# TranslationDir8Chan.net
KiCad netlist of a schematic drawn in Altium Designer
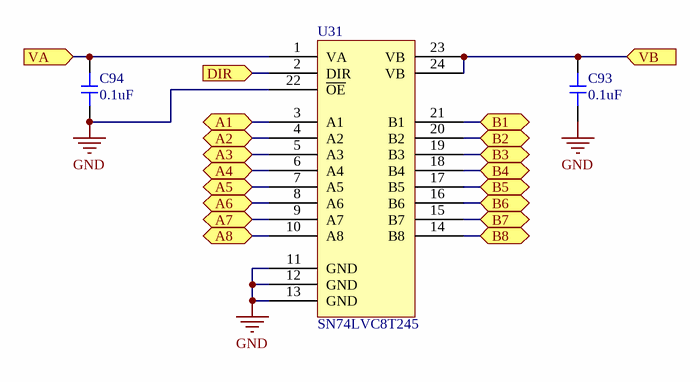
[diagram p0: TranslationDir8Chan.SchDoc]

(export (version "E")
  (design (tool "Eeschema 10.0.6"))
  (components
    (comp (ref "C93")
      (value "0.1uF")
      (footprint "0603-CAP")
      (description "Capacitor")
      (libsource (lib "AMDC") (part "Capacitor"))
    )
    (comp (ref "C94")
      (value "0.1uF")
      (footprint "0603-CAP")
      (description "Capacitor")
      (libsource (lib "AMDC") (part "Capacitor"))
    )
    (comp (ref "U31")
      (value "SN74LVC8T245")
      (footprint "TSOP65P640X120-24N")
      (description "IC BUS TRANSCVR 8BIT 24TSSOP")
      (libsource (lib "AMDC") (part "SN74LVC8T245PWR"))
    )
  )
  (nets
    (net (code "1") (name "/A1") (class "Default")
      (node (ref "U31") (pin "3") (pinfunction "A1_3") (pintype "passive"))
    )
    (net (code "2") (name "/A2") (class "Default")
      (node (ref "U31") (pin "4") (pinfunction "A2_4") (pintype "passive"))
    )
    (net (code "3") (name "/A3") (class "Default")
      (node (ref "U31") (pin "5") (pinfunction "A3_5") (pintype "passive"))
    )
    (net (code "4") (name "/A4") (class "Default")
      (node (ref "U31") (pin "6") (pinfunction "A4_6") (pintype "passive"))
    )
    (net (code "5") (name "/A5") (class "Default")
      (node (ref "U31") (pin "7") (pinfunction "A5_7") (pintype "passive"))
    )
    (net (code "6") (name "/A6") (class "Default")
      (node (ref "U31") (pin "8") (pinfunction "A6_8") (pintype "passive"))
    )
    (net (code "7") (name "/A7") (class "Default")
      (node (ref "U31") (pin "9") (pinfunction "A7_9") (pintype "passive"))
    )
    (net (code "8") (name "/A8") (class "Default")
      (node (ref "U31") (pin "10") (pinfunction "A8_10") (pintype "passive"))
    )
    (net (code "9") (name "/B1") (class "Default")
      (node (ref "U31") (pin "21") (pinfunction "B1_21") (pintype "passive"))
    )
    (net (code "10") (name "/B2") (class "Default")
      (node (ref "U31") (pin "20") (pinfunction "B2_20") (pintype "passive"))
    )
    (net (code "11") (name "/B3") (class "Default")
      (node (ref "U31") (pin "19") (pinfunction "B3_19") (pintype "passive"))
    )
    (net (code "12") (name "/B4") (class "Default")
      (node (ref "U31") (pin "18") (pinfunction "B4_18") (pintype "passive"))
    )
    (net (code "13") (name "/B5") (class "Default")
      (node (ref "U31") (pin "17") (pinfunction "B5_17") (pintype "passive"))
    )
    (net (code "14") (name "/B6") (class "Default")
      (node (ref "U31") (pin "16") (pinfunction "B6_16") (pintype "passive"))
    )
    (net (code "15") (name "/B7") (class "Default")
      (node (ref "U31") (pin "15") (pinfunction "B7_15") (pintype "passive"))
    )
    (net (code "16") (name "/B8") (class "Default")
      (node (ref "U31") (pin "14") (pinfunction "B8_14") (pintype "passive"))
    )
    (net (code "17") (name "/DIR") (class "Default")
      (node (ref "U31") (pin "2") (pinfunction "DIR_2") (pintype "passive"))
    )
    (net (code "18") (name "/VA") (class "Default")
      (node (ref "C94") (pin "1") (pinfunction "1_1") (pintype "passive"))
      (node (ref "U31") (pin "1") (pinfunction "VA_1") (pintype "passive"))
    )
    (net (code "19") (name "/VB") (class "Default")
      (node (ref "C93") (pin "1") (pinfunction "1_1") (pintype "passive"))
      (node (ref "U31") (pin "23") (pinfunction "VB_23") (pintype "passive"))
      (node (ref "U31") (pin "24") (pinfunction "VB_24") (pintype "passive"))
    )
    (net (code "20") (name "GND") (class "Default")
      (node (ref "C93") (pin "2") (pinfunction "2_2") (pintype "passive"))
      (node (ref "C94") (pin "2") (pinfunction "2_2") (pintype "passive"))
      (node (ref "U31") (pin "11") (pinfunction "GND_11") (pintype "passive"))
      (node (ref "U31") (pin "12") (pinfunction "GND_12") (pintype "passive"))
      (node (ref "U31") (pin "13") (pinfunction "GND_13") (pintype "passive"))
      (node (ref "U31") (pin "22") (pinfunction "~{OE}_22") (pintype "passive"))
    )
  )
)
